# dlp_vco_dualosc_v1_0.net
KiCad netlist of a schematic drawn in EAGLE
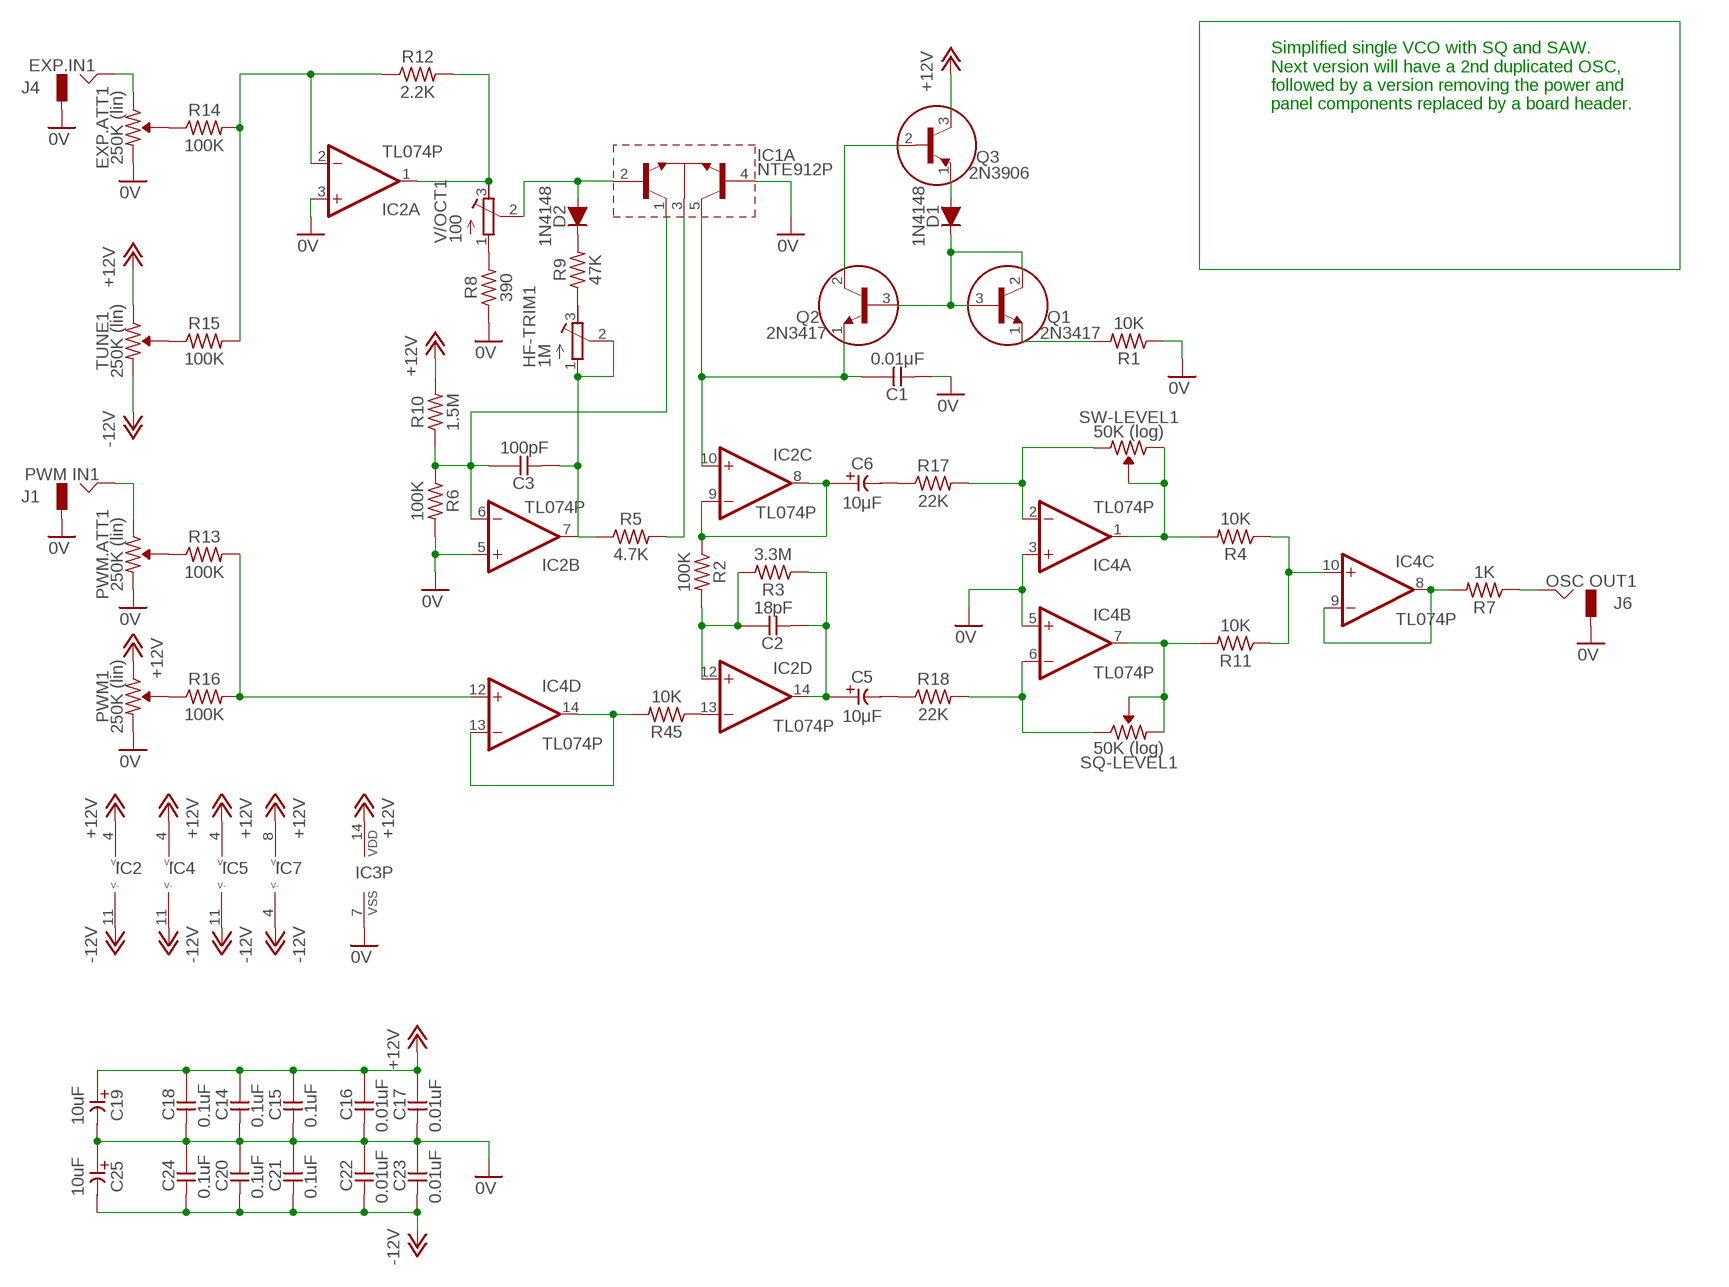
[diagram p0: schematic, sheet 1]

(export (version "E")
  (design (tool "Eeschema 10.0.6"))
  (components
    (comp (ref "C1")
      (value "0.01μF")
      (footprint "eagle-import:C025-024X044")
      (libsource (lib "eagle-import") (part "CC-US025-024X044"))
    )
    (comp (ref "C2")
      (value "18pF")
      (footprint "eagle-import:C025-024X044")
      (libsource (lib "eagle-import") (part "CC-US025-024X044"))
    )
    (comp (ref "C3")
      (value "100pF")
      (footprint "eagle-import:C025-024X044")
      (libsource (lib "eagle-import") (part "CC-US025-024X044"))
    )
    (comp (ref "C5")
      (value "10μF")
      (footprint "eagle-import:E2-5")
      (libsource (lib "eagle-import") (part "CE-USE2-5"))
    )
    (comp (ref "C6")
      (value "10μF")
      (footprint "eagle-import:E2-5")
      (libsource (lib "eagle-import") (part "CE-USE2-5"))
    )
    (comp (ref "C14")
      (value "0.1uF")
      (footprint "eagle-import:C025-024X044")
      (libsource (lib "eagle-import") (part "CC-US025-024X044"))
    )
    (comp (ref "C15")
      (value "0.1uF")
      (footprint "eagle-import:C025-024X044")
      (libsource (lib "eagle-import") (part "CC-US025-024X044"))
    )
    (comp (ref "C16")
      (value "0.01uF")
      (footprint "eagle-import:C025-024X044")
      (libsource (lib "eagle-import") (part "CC-US025-024X044"))
    )
    (comp (ref "C17")
      (value "0.01uF")
      (footprint "eagle-import:C025-024X044")
      (libsource (lib "eagle-import") (part "CC-US025-024X044"))
    )
    (comp (ref "C18")
      (value "0.1uF")
      (footprint "eagle-import:C025-024X044")
      (libsource (lib "eagle-import") (part "CC-US025-024X044"))
    )
    (comp (ref "C19")
      (value "10uF")
      (footprint "eagle-import:E2-5")
      (libsource (lib "eagle-import") (part "CE-USE2-5"))
    )
    (comp (ref "C20")
      (value "0.1uF")
      (footprint "eagle-import:C025-024X044")
      (libsource (lib "eagle-import") (part "CC-US025-024X044"))
    )
    (comp (ref "C21")
      (value "0.1uF")
      (footprint "eagle-import:C025-024X044")
      (libsource (lib "eagle-import") (part "CC-US025-024X044"))
    )
    (comp (ref "C22")
      (value "0.01uF")
      (footprint "eagle-import:C025-024X044")
      (libsource (lib "eagle-import") (part "CC-US025-024X044"))
    )
    (comp (ref "C23")
      (value "0.01uF")
      (footprint "eagle-import:C025-024X044")
      (libsource (lib "eagle-import") (part "CC-US025-024X044"))
    )
    (comp (ref "C24")
      (value "0.1uF")
      (footprint "eagle-import:C025-024X044")
      (libsource (lib "eagle-import") (part "CC-US025-024X044"))
    )
    (comp (ref "C25")
      (value "10uF")
      (footprint "eagle-import:E2-5")
      (libsource (lib "eagle-import") (part "CE-USE2-5"))
    )
    (comp (ref "D1")
      (value "1N4148")
      (footprint "eagle-import:DO35-7")
      (libsource (lib "eagle-import") (part "1N4148"))
    )
    (comp (ref "D2")
      (value "1N4148")
      (footprint "eagle-import:DO35-7")
      (libsource (lib "eagle-import") (part "1N4148"))
    )
    (comp (ref "EXP.ATT1")
      (value "250K (lin)")
      (footprint "eagle-import:R-VAR")
      (libsource (lib "eagle-import") (part "R-VAR"))
    )
    (comp (ref "HF-TRIM1")
      (value "1M")
      (footprint "eagle-import:RTRIM3296Y")
      (libsource (lib "eagle-import") (part "R-TRIMM3296Y"))
    )
    (comp (ref "IC1")
      (value "NTE912P")
      (footprint "eagle-import:DIL14")
      (libsource (lib "eagle-import") (part "NTE912P"))
    )
    (comp (ref "IC2")
      (value "TL074P")
      (footprint "eagle-import:DIL14")
      (libsource (lib "eagle-import") (part "TL074P"))
    )
    (comp (ref "IC3")
      (value "4013N")
      (footprint "eagle-import:DIL14")
      (libsource (lib "eagle-import") (part "4013N"))
    )
    (comp (ref "IC4")
      (value "TL074P")
      (footprint "eagle-import:DIL14")
      (libsource (lib "eagle-import") (part "TL074P"))
    )
    (comp (ref "IC5")
      (value "TL074P")
      (footprint "eagle-import:DIL14")
      (libsource (lib "eagle-import") (part "TL074P"))
    )
    (comp (ref "IC7")
      (value "TL072P")
      (footprint "eagle-import:DIL08")
      (libsource (lib "eagle-import") (part "TL072P"))
    )
    (comp (ref "J1")
      (value "PWM IN1")
      (footprint "eagle-import:JACK-M")
      (libsource (lib "eagle-import") (part "JACK-M"))
    )
    (comp (ref "J4")
      (value "EXP.IN1")
      (footprint "eagle-import:JACK-M")
      (libsource (lib "eagle-import") (part "JACK-M"))
    )
    (comp (ref "J6")
      (value "OSC OUT1")
      (footprint "eagle-import:JACK-M")
      (libsource (lib "eagle-import") (part "JACK-M"))
    )
    (comp (ref "PWM.ATT1")
      (value "250K (lin)")
      (footprint "eagle-import:R-VAR")
      (libsource (lib "eagle-import") (part "R-VAR"))
    )
    (comp (ref "PWM1")
      (value "250K (lin)")
      (footprint "eagle-import:R-VAR")
      (libsource (lib "eagle-import") (part "R-VAR"))
    )
    (comp (ref "Q1")
      (value "2N3417")
      (footprint "eagle-import:TO92")
      (libsource (lib "eagle-import") (part "2N3417"))
    )
    (comp (ref "Q2")
      (value "2N3417")
      (footprint "eagle-import:TO92")
      (libsource (lib "eagle-import") (part "2N3417"))
    )
    (comp (ref "Q3")
      (value "2N3906")
      (footprint "eagle-import:TO92")
      (libsource (lib "eagle-import") (part "2N3906"))
    )
    (comp (ref "R1")
      (value "10K")
      (footprint "eagle-import:0309_10")
      (libsource (lib "eagle-import") (part "R0309/10"))
    )
    (comp (ref "R2")
      (value "100K")
      (footprint "eagle-import:0309_10")
      (libsource (lib "eagle-import") (part "R0309/10"))
    )
    (comp (ref "R3")
      (value "3.3M")
      (footprint "eagle-import:0309_10")
      (libsource (lib "eagle-import") (part "R0309/10"))
    )
    (comp (ref "R4")
      (value "10K")
      (footprint "eagle-import:0309_10")
      (libsource (lib "eagle-import") (part "R0309/10"))
    )
    (comp (ref "R5")
      (value "4.7K")
      (footprint "eagle-import:0309_10")
      (libsource (lib "eagle-import") (part "R0309/10"))
    )
    (comp (ref "R6")
      (value "100K")
      (footprint "eagle-import:0309_10")
      (libsource (lib "eagle-import") (part "R0309/10"))
    )
    (comp (ref "R7")
      (value "1K")
      (footprint "eagle-import:0309_10")
      (libsource (lib "eagle-import") (part "R0309/10"))
    )
    (comp (ref "R8")
      (value "390")
      (footprint "eagle-import:0309_10")
      (libsource (lib "eagle-import") (part "R0309/10"))
    )
    (comp (ref "R9")
      (value "47K")
      (footprint "eagle-import:0309_10")
      (libsource (lib "eagle-import") (part "R0309/10"))
    )
    (comp (ref "R10")
      (value "1.5M")
      (footprint "eagle-import:0309_10")
      (libsource (lib "eagle-import") (part "R0309/10"))
    )
    (comp (ref "R11")
      (value "10K")
      (footprint "eagle-import:0309_10")
      (libsource (lib "eagle-import") (part "R0309/10"))
    )
    (comp (ref "R12")
      (value "2.2K")
      (footprint "eagle-import:0309_10")
      (libsource (lib "eagle-import") (part "R0309/10"))
    )
    (comp (ref "R13")
      (value "100K")
      (footprint "eagle-import:0309_10")
      (libsource (lib "eagle-import") (part "R0309/10"))
    )
    (comp (ref "R14")
      (value "100K")
      (footprint "eagle-import:0309_10")
      (libsource (lib "eagle-import") (part "R0309/10"))
    )
    (comp (ref "R15")
      (value "100K")
      (footprint "eagle-import:0309_10")
      (libsource (lib "eagle-import") (part "R0309/10"))
    )
    (comp (ref "R16")
      (value "100K")
      (footprint "eagle-import:0309_10")
      (libsource (lib "eagle-import") (part "R0309/10"))
    )
    (comp (ref "R17")
      (value "22K")
      (footprint "eagle-import:0309_10")
      (libsource (lib "eagle-import") (part "R0309/10"))
    )
    (comp (ref "R18")
      (value "22K")
      (footprint "eagle-import:0309_10")
      (libsource (lib "eagle-import") (part "R0309/10"))
    )
    (comp (ref "R45")
      (value "10K")
      (footprint "eagle-import:0309_10")
      (libsource (lib "eagle-import") (part "R0309/10"))
    )
    (comp (ref "SQ-LEVEL1")
      (value "50K (log)")
      (footprint "eagle-import:R-VAR")
      (libsource (lib "eagle-import") (part "R-VAR"))
    )
    (comp (ref "SW-LEVEL1")
      (value "50K (log)")
      (footprint "eagle-import:R-VAR")
      (libsource (lib "eagle-import") (part "R-VAR"))
    )
    (comp (ref "TUNE1")
      (value "250K (lin)")
      (footprint "eagle-import:R-VAR")
      (libsource (lib "eagle-import") (part "R-VAR"))
    )
    (comp (ref "V/OCT1")
      (value "100")
      (footprint "eagle-import:RTRIM3296Y")
      (libsource (lib "eagle-import") (part "R-TRIMM3296Y"))
    )
  )
  (nets
    (net (code "1") (name "+12V") (class "Default")
      (node (ref "C14") (pin "1") (pinfunction "1_1") (pintype "passive"))
      (node (ref "C15") (pin "1") (pinfunction "1_1") (pintype "passive"))
      (node (ref "C16") (pin "1") (pinfunction "1_1") (pintype "passive"))
      (node (ref "C17") (pin "1") (pinfunction "1_1") (pintype "passive"))
      (node (ref "C18") (pin "1") (pinfunction "1_1") (pintype "passive"))
      (node (ref "C19") (pin "+") (pinfunction "+_+") (pintype "passive"))
      (node (ref "IC2") (pin "4") (pinfunction "V+_4") (pintype "power_in"))
      (node (ref "IC3") (pin "14") (pinfunction "VDD_14") (pintype "power_in"))
      (node (ref "IC4") (pin "4") (pinfunction "V+_4") (pintype "power_in"))
      (node (ref "IC5") (pin "4") (pinfunction "V+_4") (pintype "power_in"))
      (node (ref "IC7") (pin "8") (pinfunction "V+_8") (pintype "power_in"))
      (node (ref "PWM1") (pin "R1") (pinfunction "1_R1") (pintype "passive"))
      (node (ref "Q3") (pin "3") (pinfunction "C_3") (pintype "passive"))
      (node (ref "R10") (pin "2") (pinfunction "2_2") (pintype "passive"))
      (node (ref "TUNE1") (pin "R1") (pinfunction "1_R1") (pintype "passive"))
    )
    (net (code "2") (name "-12V") (class "Default")
      (node (ref "C20") (pin "2") (pinfunction "2_2") (pintype "passive"))
      (node (ref "C21") (pin "2") (pinfunction "2_2") (pintype "passive"))
      (node (ref "C22") (pin "2") (pinfunction "2_2") (pintype "passive"))
      (node (ref "C23") (pin "2") (pinfunction "2_2") (pintype "passive"))
      (node (ref "C24") (pin "2") (pinfunction "2_2") (pintype "passive"))
      (node (ref "C25") (pin "-") (pinfunction "-_-") (pintype "passive"))
      (node (ref "IC2") (pin "11") (pinfunction "V-_11") (pintype "power_in"))
      (node (ref "IC4") (pin "11") (pinfunction "V-_11") (pintype "power_in"))
      (node (ref "IC5") (pin "11") (pinfunction "V-_11") (pintype "power_in"))
      (node (ref "IC7") (pin "4") (pinfunction "V-_4") (pintype "power_in"))
      (node (ref "TUNE1") (pin "R2") (pinfunction "2_R2") (pintype "passive"))
    )
    (net (code "3") (name "0V") (class "Default")
      (node (ref "C1") (pin "2") (pinfunction "2_2") (pintype "passive"))
      (node (ref "C14") (pin "2") (pinfunction "2_2") (pintype "passive"))
      (node (ref "C15") (pin "2") (pinfunction "2_2") (pintype "passive"))
      (node (ref "C16") (pin "2") (pinfunction "2_2") (pintype "passive"))
      (node (ref "C17") (pin "2") (pinfunction "2_2") (pintype "passive"))
      (node (ref "C18") (pin "2") (pinfunction "2_2") (pintype "passive"))
      (node (ref "C19") (pin "-") (pinfunction "-_-") (pintype "passive"))
      (node (ref "C20") (pin "1") (pinfunction "1_1") (pintype "passive"))
      (node (ref "C21") (pin "1") (pinfunction "1_1") (pintype "passive"))
      (node (ref "C22") (pin "1") (pinfunction "1_1") (pintype "passive"))
      (node (ref "C23") (pin "1") (pinfunction "1_1") (pintype "passive"))
      (node (ref "C24") (pin "1") (pinfunction "1_1") (pintype "passive"))
      (node (ref "C25") (pin "+") (pinfunction "+_+") (pintype "passive"))
      (node (ref "EXP.ATT1") (pin "R2") (pinfunction "2_R2") (pintype "passive"))
      (node (ref "IC1") (pin "4") (pinfunction "B3_4") (pintype "passive"))
      (node (ref "IC2") (pin "3") (pinfunction "+IN_3") (pintype "input"))
      (node (ref "IC2") (pin "5") (pinfunction "+IN_5") (pintype "input"))
      (node (ref "IC3") (pin "7") (pinfunction "VSS_7") (pintype "power_in"))
      (node (ref "IC4") (pin "3") (pinfunction "+IN_3") (pintype "input"))
      (node (ref "IC4") (pin "5") (pinfunction "+IN_5") (pintype "input"))
      (node (ref "J1") (pin "GND") (pinfunction "GND_GND") (pintype "bidirectional"))
      (node (ref "J4") (pin "GND") (pinfunction "GND_GND") (pintype "bidirectional"))
      (node (ref "J6") (pin "GND") (pinfunction "GND_GND") (pintype "bidirectional"))
      (node (ref "PWM.ATT1") (pin "R2") (pinfunction "2_R2") (pintype "passive"))
      (node (ref "PWM1") (pin "R2") (pinfunction "2_R2") (pintype "passive"))
      (node (ref "R1") (pin "1") (pinfunction "1_1") (pintype "passive"))
      (node (ref "R6") (pin "2") (pinfunction "2_2") (pintype "passive"))
      (node (ref "R8") (pin "1") (pinfunction "1_1") (pintype "passive"))
    )
    (net (code "4") (name "Net-(C5-Pad-)") (class "Default")
      (node (ref "C5") (pin "-") (pinfunction "-_-") (pintype "passive"))
      (node (ref "R18") (pin "1") (pinfunction "1_1") (pintype "passive"))
    )
    (net (code "5") (name "Net-(C6-Pad-)") (class "Default")
      (node (ref "C6") (pin "-") (pinfunction "-_-") (pintype "passive"))
      (node (ref "R17") (pin "1") (pinfunction "1_1") (pintype "passive"))
    )
    (net (code "6") (name "Net-(D2-PadC)") (class "Default")
      (node (ref "D2") (pin "C") (pinfunction "C_C") (pintype "passive"))
      (node (ref "R9") (pin "2") (pinfunction "2_2") (pintype "passive"))
    )
    (net (code "7") (name "Net-(EXP.ATT1-1)") (class "Default")
      (node (ref "EXP.ATT1") (pin "R1") (pinfunction "1_R1") (pintype "passive"))
      (node (ref "J4") (pin "HOT") (pinfunction "HOT_HOT") (pintype "bidirectional"))
    )
    (net (code "8") (name "Net-(EXP.ATT1-P$1)") (class "Default")
      (node (ref "EXP.ATT1") (pin "VAR") (pinfunction "P$1_VAR") (pintype "passive"))
      (node (ref "R14") (pin "1") (pinfunction "1_1") (pintype "passive"))
    )
    (net (code "9") (name "Net-(HF-TRIM1-A)") (class "Default")
      (node (ref "C3") (pin "2") (pinfunction "2_2") (pintype "passive"))
      (node (ref "HF-TRIM1") (pin "1") (pinfunction "A_1") (pintype "passive"))
      (node (ref "HF-TRIM1") (pin "2") (pinfunction "S_2") (pintype "passive"))
      (node (ref "IC2") (pin "7") (pinfunction "OUT_7") (pintype "output"))
      (node (ref "R5") (pin "1") (pinfunction "1_1") (pintype "passive"))
    )
    (net (code "10") (name "Net-(HF-TRIM1-E)") (class "Default")
      (node (ref "HF-TRIM1") (pin "3") (pinfunction "E_3") (pintype "passive"))
      (node (ref "R9") (pin "1") (pinfunction "1_1") (pintype "passive"))
    )
    (net (code "11") (name "Net-(IC1A-B1)") (class "Default")
      (node (ref "D2") (pin "A") (pinfunction "A_A") (pintype "passive"))
      (node (ref "IC1") (pin "2") (pinfunction "B1_2") (pintype "passive"))
      (node (ref "V/OCT1") (pin "2") (pinfunction "S_2") (pintype "passive"))
    )
    (net (code "12") (name "Net-(IC1A-C1)") (class "Default")
      (node (ref "C3") (pin "1") (pinfunction "1_1") (pintype "passive"))
      (node (ref "IC1") (pin "1") (pinfunction "C1_1") (pintype "passive"))
      (node (ref "IC2") (pin "6") (pinfunction "-IN_6") (pintype "input"))
      (node (ref "R10") (pin "1") (pinfunction "1_1") (pintype "passive"))
      (node (ref "R6") (pin "1") (pinfunction "1_1") (pintype "passive"))
    )
    (net (code "13") (name "Net-(IC1A-C3)") (class "Default")
      (node (ref "C1") (pin "1") (pinfunction "1_1") (pintype "passive"))
      (node (ref "IC1") (pin "5") (pinfunction "C3_5") (pintype "passive"))
      (node (ref "IC2") (pin "10") (pinfunction "+IN_10") (pintype "input"))
      (node (ref "Q2") (pin "1") (pinfunction "E_1") (pintype "passive"))
    )
    (net (code "14") (name "Net-(IC1A-E)") (class "Default")
      (node (ref "IC1") (pin "3") (pinfunction "E_3") (pintype "passive"))
      (node (ref "R5") (pin "2") (pinfunction "2_2") (pintype "passive"))
    )
    (net (code "15") (name "Net-(IC2A--IN)") (class "Default")
      (node (ref "IC2") (pin "2") (pinfunction "-IN_2") (pintype "input"))
      (node (ref "R12") (pin "1") (pinfunction "1_1") (pintype "passive"))
      (node (ref "R14") (pin "2") (pinfunction "2_2") (pintype "passive"))
      (node (ref "R15") (pin "2") (pinfunction "2_2") (pintype "passive"))
    )
    (net (code "16") (name "Net-(IC2A-OUT)") (class "Default")
      (node (ref "IC2") (pin "1") (pinfunction "OUT_1") (pintype "output"))
      (node (ref "R12") (pin "2") (pinfunction "2_2") (pintype "passive"))
      (node (ref "V/OCT1") (pin "3") (pinfunction "E_3") (pintype "passive"))
    )
    (net (code "17") (name "Net-(IC2C--IN)") (class "Default")
      (node (ref "C6") (pin "+") (pinfunction "+_+") (pintype "passive"))
      (node (ref "IC2") (pin "8") (pinfunction "OUT_8") (pintype "output"))
      (node (ref "IC2") (pin "9") (pinfunction "-IN_9") (pintype "input"))
      (node (ref "R2") (pin "1") (pinfunction "1_1") (pintype "passive"))
    )
    (net (code "18") (name "Net-(IC2D-+IN)") (class "Default")
      (node (ref "C2") (pin "1") (pinfunction "1_1") (pintype "passive"))
      (node (ref "IC2") (pin "12") (pinfunction "+IN_12") (pintype "input"))
      (node (ref "R2") (pin "2") (pinfunction "2_2") (pintype "passive"))
      (node (ref "R3") (pin "2") (pinfunction "2_2") (pintype "passive"))
    )
    (net (code "19") (name "Net-(IC2D--IN)") (class "Default")
      (node (ref "IC2") (pin "13") (pinfunction "-IN_13") (pintype "input"))
      (node (ref "R45") (pin "1") (pinfunction "1_1") (pintype "passive"))
    )
    (net (code "20") (name "Net-(IC2D-OUT)") (class "Default")
      (node (ref "C2") (pin "2") (pinfunction "2_2") (pintype "passive"))
      (node (ref "C5") (pin "+") (pinfunction "+_+") (pintype "passive"))
      (node (ref "IC2") (pin "14") (pinfunction "OUT_14") (pintype "output"))
      (node (ref "R3") (pin "1") (pinfunction "1_1") (pintype "passive"))
    )
    (net (code "21") (name "Net-(IC4A--IN)") (class "Default")
      (node (ref "IC4") (pin "2") (pinfunction "-IN_2") (pintype "input"))
      (node (ref "R17") (pin "2") (pinfunction "2_2") (pintype "passive"))
      (node (ref "SW-LEVEL1") (pin "R2") (pinfunction "2_R2") (pintype "passive"))
    )
    (net (code "22") (name "Net-(IC4A-OUT)") (class "Default")
      (node (ref "IC4") (pin "1") (pinfunction "OUT_1") (pintype "output"))
      (node (ref "R4") (pin "2") (pinfunction "2_2") (pintype "passive"))
      (node (ref "SW-LEVEL1") (pin "R1") (pinfunction "1_R1") (pintype "passive"))
      (node (ref "SW-LEVEL1") (pin "VAR") (pinfunction "P$1_VAR") (pintype "passive"))
    )
    (net (code "23") (name "Net-(IC4B--IN)") (class "Default")
      (node (ref "IC4") (pin "6") (pinfunction "-IN_6") (pintype "input"))
      (node (ref "R18") (pin "2") (pinfunction "2_2") (pintype "passive"))
      (node (ref "SQ-LEVEL1") (pin "R1") (pinfunction "1_R1") (pintype "passive"))
    )
    (net (code "24") (name "Net-(IC4B-OUT)") (class "Default")
      (node (ref "IC4") (pin "7") (pinfunction "OUT_7") (pintype "output"))
      (node (ref "R11") (pin "2") (pinfunction "2_2") (pintype "passive"))
      (node (ref "SQ-LEVEL1") (pin "R2") (pinfunction "2_R2") (pintype "passive"))
      (node (ref "SQ-LEVEL1") (pin "VAR") (pinfunction "P$1_VAR") (pintype "passive"))
    )
    (net (code "25") (name "Net-(IC4C-+IN)") (class "Default")
      (node (ref "IC4") (pin "10") (pinfunction "+IN_10") (pintype "input"))
      (node (ref "R11") (pin "1") (pinfunction "1_1") (pintype "passive"))
      (node (ref "R4") (pin "1") (pinfunction "1_1") (pintype "passive"))
    )
    (net (code "26") (name "Net-(IC4C--IN)") (class "Default")
      (node (ref "IC4") (pin "8") (pinfunction "OUT_8") (pintype "output"))
      (node (ref "IC4") (pin "9") (pinfunction "-IN_9") (pintype "input"))
      (node (ref "R7") (pin "2") (pinfunction "2_2") (pintype "passive"))
    )
    (net (code "27") (name "Net-(IC4D-+IN)") (class "Default")
      (node (ref "IC4") (pin "12") (pinfunction "+IN_12") (pintype "input"))
      (node (ref "R13") (pin "2") (pinfunction "2_2") (pintype "passive"))
      (node (ref "R16") (pin "2") (pinfunction "2_2") (pintype "passive"))
    )
    (net (code "28") (name "Net-(IC4D--IN)") (class "Default")
      (node (ref "IC4") (pin "13") (pinfunction "-IN_13") (pintype "input"))
      (node (ref "IC4") (pin "14") (pinfunction "OUT_14") (pintype "output"))
      (node (ref "R45") (pin "2") (pinfunction "2_2") (pintype "passive"))
    )
    (net (code "29") (name "Net-(J6-PadHOT)") (class "Default")
      (node (ref "J6") (pin "HOT") (pinfunction "HOT_HOT") (pintype "bidirectional"))
      (node (ref "R7") (pin "1") (pinfunction "1_1") (pintype "passive"))
    )
    (net (code "30") (name "Net-(PWM.ATT1-1)") (class "Default")
      (node (ref "J1") (pin "HOT") (pinfunction "HOT_HOT") (pintype "bidirectional"))
      (node (ref "PWM.ATT1") (pin "R1") (pinfunction "1_R1") (pintype "passive"))
    )
    (net (code "31") (name "Net-(PWM.ATT1-P$1)") (class "Default")
      (node (ref "PWM.ATT1") (pin "VAR") (pinfunction "P$1_VAR") (pintype "passive"))
      (node (ref "R13") (pin "1") (pinfunction "1_1") (pintype "passive"))
    )
    (net (code "32") (name "Net-(PWM1-P$1)") (class "Default")
      (node (ref "PWM1") (pin "VAR") (pinfunction "P$1_VAR") (pintype "passive"))
      (node (ref "R16") (pin "1") (pinfunction "1_1") (pintype "passive"))
    )
    (net (code "33") (name "Net-(Q1-B)") (class "Default")
      (node (ref "D1") (pin "C") (pinfunction "C_C") (pintype "passive"))
      (node (ref "Q1") (pin "2") (pinfunction "C_2") (pintype "passive"))
      (node (ref "Q1") (pin "3") (pinfunction "B_3") (pintype "passive"))
      (node (ref "Q2") (pin "3") (pinfunction "B_3") (pintype "passive"))
    )
    (net (code "34") (name "Net-(Q1-E)") (class "Default")
      (node (ref "Q1") (pin "1") (pinfunction "E_1") (pintype "passive"))
      (node (ref "R1") (pin "2") (pinfunction "2_2") (pintype "passive"))
    )
    (net (code "35") (name "Net-(Q2-C)") (class "Default")
      (node (ref "Q2") (pin "2") (pinfunction "C_2") (pintype "passive"))
      (node (ref "Q3") (pin "2") (pinfunction "B_2") (pintype "passive"))
    )
    (net (code "36") (name "Net-(Q3-E)") (class "Default")
      (node (ref "D1") (pin "A") (pinfunction "A_A") (pintype "passive"))
      (node (ref "Q3") (pin "1") (pinfunction "E_1") (pintype "passive"))
    )
    (net (code "37") (name "Net-(TUNE1-P$1)") (class "Default")
      (node (ref "R15") (pin "1") (pinfunction "1_1") (pintype "passive"))
      (node (ref "TUNE1") (pin "VAR") (pinfunction "P$1_VAR") (pintype "passive"))
    )
    (net (code "38") (name "Net-(V/OCT1-A)") (class "Default")
      (node (ref "R8") (pin "2") (pinfunction "2_2") (pintype "passive"))
      (node (ref "V/OCT1") (pin "1") (pinfunction "A_1") (pintype "passive"))
    )
  )
)
